# 4-Antennas.net
KiCad netlist of a schematic drawn in Altium Designer
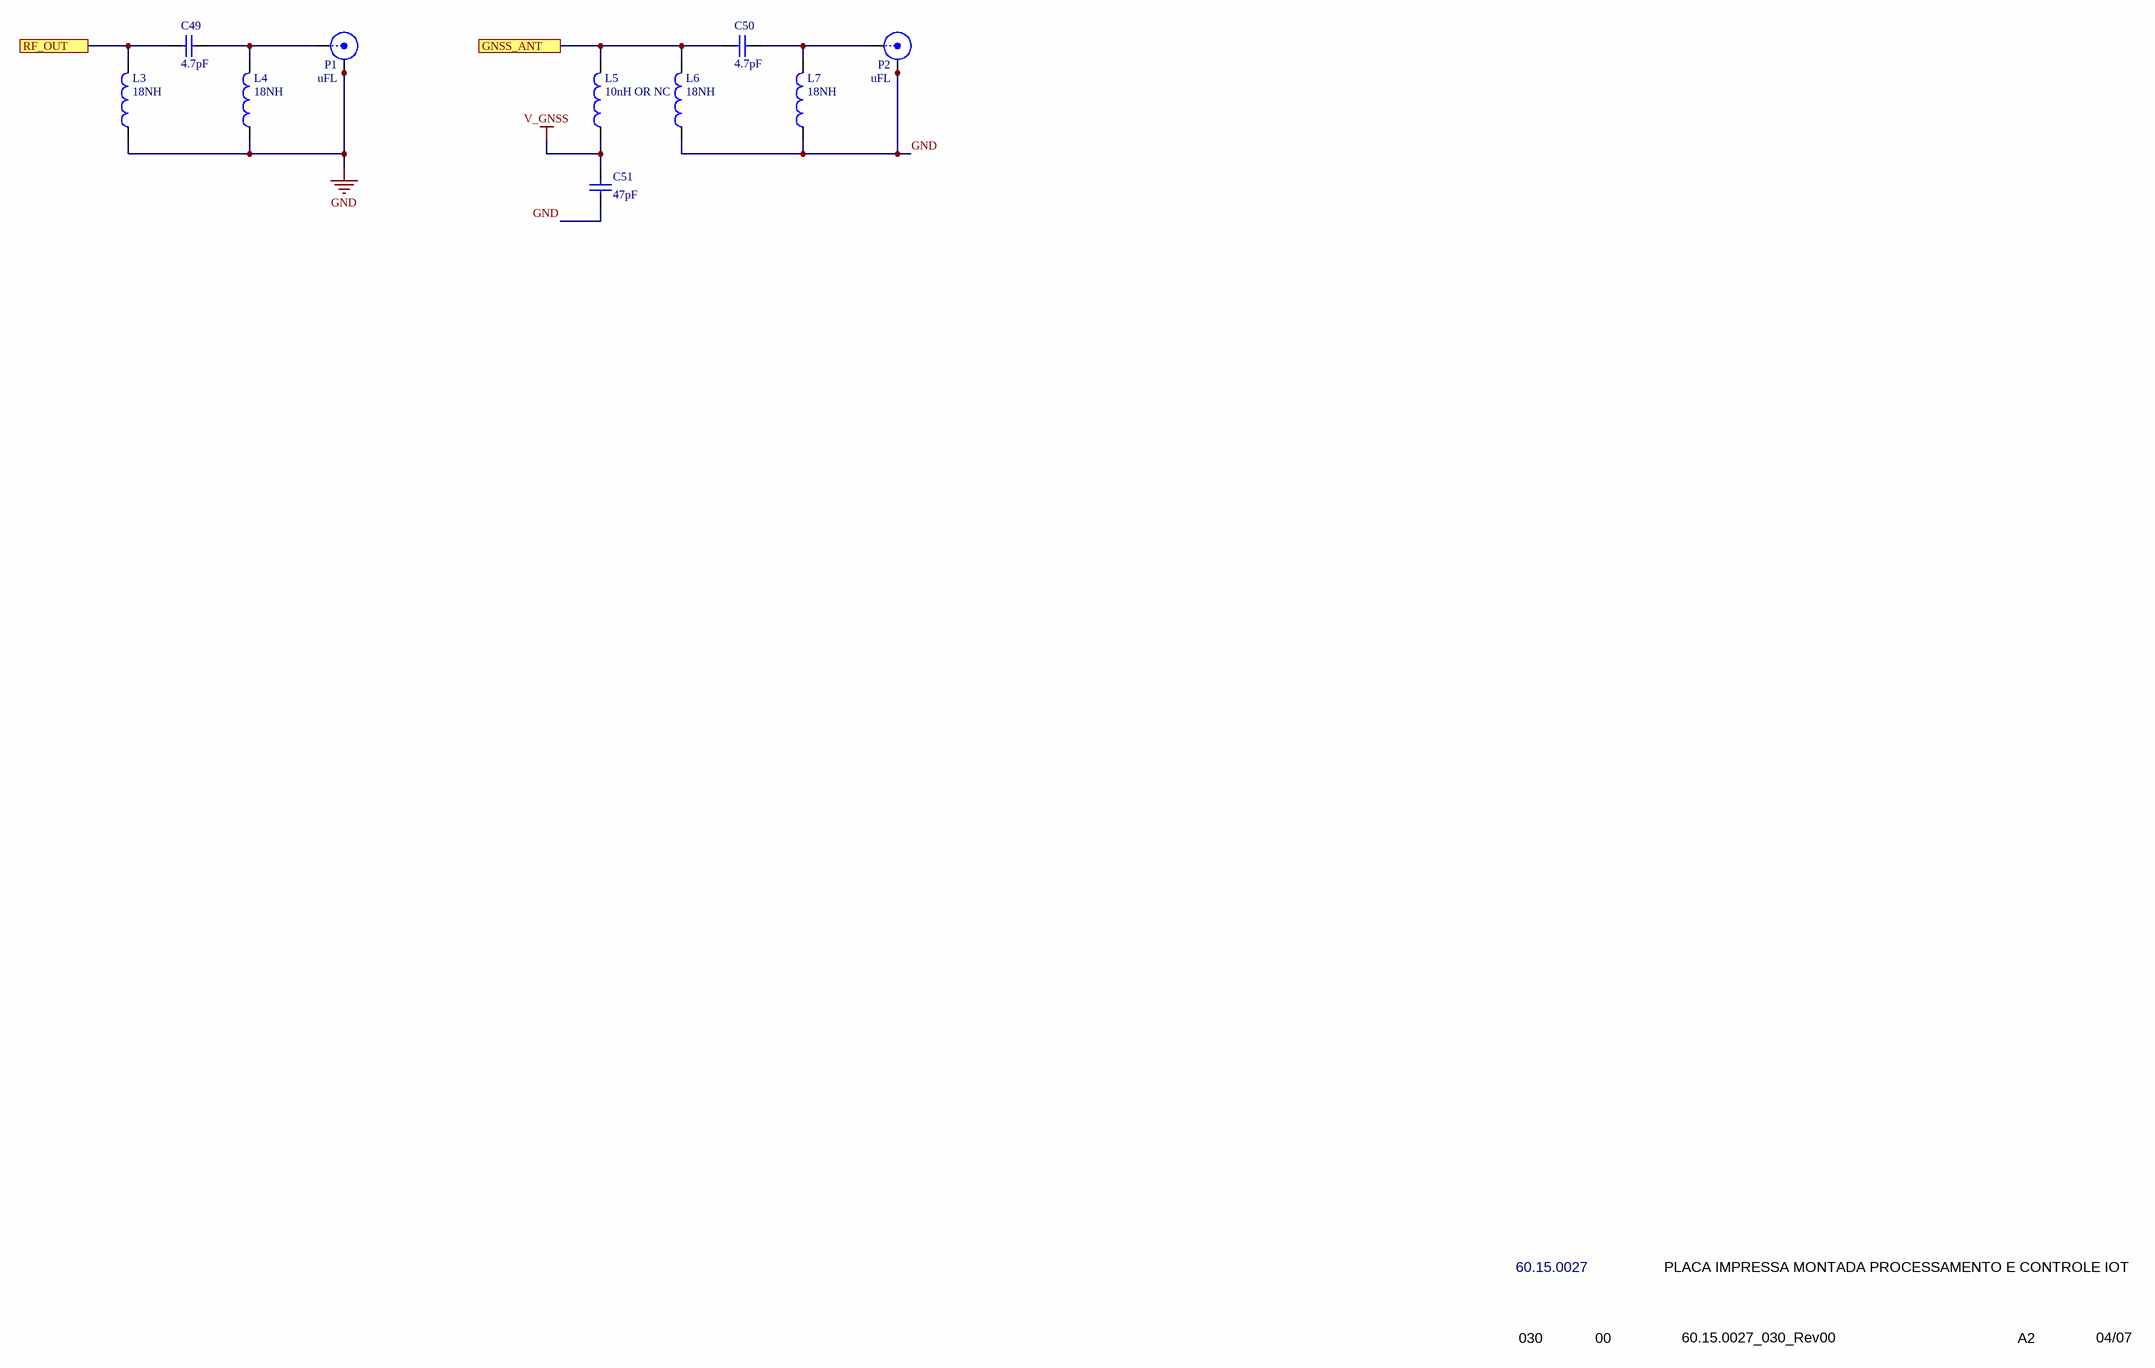
[diagram p0: 4-Antennas.SchDoc]

(export (version "E")
  (design (tool "Eeschema 10.0.6"))
  (components
    (comp (ref "C49")
      (value "16.23.0788")
      (footprint "16.23.0788")
      (description "CAPACITOR CERAMICO MULTICAMADA 4.7PF 50V C0G/NP0 0402")
      (fields (field (name "ALTIUM_UNNAMED_1") "4.7pF"))
      (libsource (lib "OMNI-CAPACITORES") (part "16.23.0788"))
    )
    (comp (ref "C50")
      (value "16.23.0788")
      (footprint "16.23.0788")
      (description "CAPACITOR CERAMICO MULTICAMADA 4.7PF 50V C0G/NP0 0402")
      (fields (field (name "ALTIUM_UNNAMED_1") "4.7pF"))
      (libsource (lib "OMNI-CAPACITORES") (part "16.23.0788"))
    )
    (comp (ref "C51")
      (value "16.23.0798")
      (footprint "16.23.0798")
      (description "CAPACITOR CERAMICO 47pF 10V 5% C0G SMD 0201")
      (fields (field (name "ALTIUM_UNNAMED_1") "47pF"))
      (libsource (lib "OMNI-CAPACITORES") (part "16.23.0798"))
    )
    (comp (ref "L3")
      (value "18NH")
      (footprint "40.12.0345")
      (description "INDUTOR FIXO 18NH 370MA 270 MOHM 0402")
      (fields (field (name "Comment") "40.12.0345"))
      (libsource (lib "OMNI-INDUTORES") (part "40.12.0345"))
    )
    (comp (ref "L4")
      (value "18NH")
      (footprint "40.12.0345")
      (description "INDUTOR FIXO 18NH 370MA 270 MOHM 0402")
      (fields (field (name "Comment") "40.12.0345"))
      (libsource (lib "OMNI-INDUTORES") (part "40.12.0345"))
    )
    (comp (ref "L5")
      (value "10nH OR NC")
      (footprint "40.12.0348")
      (description "INDUTOR FIXO 10nH 3% 500mA 260mOHM 0402")
      (fields (field (name "PART NUMBER") "LQG15HS10NH02D") (field (name "Comment") "40.12.0348"))
      (libsource (lib "OMNI-INDUTORES") (part "40.12.0348"))
    )
    (comp (ref "L6")
      (value "18NH")
      (footprint "40.12.0345")
      (description "INDUTOR FIXO 18NH 370MA 270 MOHM 0402")
      (fields (field (name "Comment") "40.12.0345"))
      (libsource (lib "OMNI-INDUTORES") (part "40.12.0345"))
    )
    (comp (ref "L7")
      (value "18NH")
      (footprint "40.12.0345")
      (description "INDUTOR FIXO 18NH 370MA 270 MOHM 0402")
      (fields (field (name "Comment") "40.12.0345"))
      (libsource (lib "OMNI-INDUTORES") (part "40.12.0345"))
    )
    (comp (ref "P1")
      (value "uFL")
      (footprint "28.20.0019")
      (description "CONECTOR MICRO COAXIAL 50 OHM SMD")
      (fields (field (name "Comment") "28.20.0019"))
      (libsource (lib "OMNI-CONECTORES") (part "28.20.0019"))
    )
    (comp (ref "P2")
      (value "uFL")
      (footprint "28.20.0019")
      (description "CONECTOR MICRO COAXIAL 50 OHM SMD")
      (fields (field (name "Comment") "28.20.0019"))
      (libsource (lib "OMNI-CONECTORES") (part "28.20.0019"))
    )
  )
  (nets
    (net (code "1") (name "/GNSS_ANT") (class "Default")
      (node (ref "C50") (pin "2") (pinfunction "2_2") (pintype "passive"))
      (node (ref "L5") (pin "2") (pinfunction "2_2") (pintype "passive"))
      (node (ref "L6") (pin "2") (pinfunction "2_2") (pintype "passive"))
    )
    (net (code "2") (name "/RF_OUT") (class "Default")
      (node (ref "C49") (pin "2") (pinfunction "2_2") (pintype "passive"))
      (node (ref "L3") (pin "2") (pinfunction "2_2") (pintype "passive"))
    )
    (net (code "3") (name "GND") (class "Default")
      (node (ref "C51") (pin "1") (pinfunction "1_1") (pintype "passive"))
      (node (ref "L3") (pin "1") (pinfunction "1_1") (pintype "passive"))
      (node (ref "L4") (pin "1") (pinfunction "1_1") (pintype "passive"))
      (node (ref "L6") (pin "1") (pinfunction "1_1") (pintype "passive"))
      (node (ref "L7") (pin "1") (pinfunction "1_1") (pintype "passive"))
      (node (ref "P1") (pin "2") (pinfunction "GND_2") (pintype "power_in"))
      (node (ref "P1") (pin "3") (pinfunction "GND_3") (pintype "power_in"))
      (node (ref "P2") (pin "2") (pinfunction "GND_2") (pintype "power_in"))
      (node (ref "P2") (pin "3") (pinfunction "GND_3") (pintype "power_in"))
    )
    (net (code "4") (name "Net-(P1-SIG)") (class "Default")
      (node (ref "C49") (pin "1") (pinfunction "1_1") (pintype "passive"))
      (node (ref "L4") (pin "2") (pinfunction "2_2") (pintype "passive"))
      (node (ref "P1") (pin "1") (pinfunction "SIG_1") (pintype "passive"))
    )
    (net (code "5") (name "Net-(P2-SIG)") (class "Default")
      (node (ref "C50") (pin "1") (pinfunction "1_1") (pintype "passive"))
      (node (ref "L7") (pin "2") (pinfunction "2_2") (pintype "passive"))
      (node (ref "P2") (pin "1") (pinfunction "SIG_1") (pintype "passive"))
    )
    (net (code "6") (name "V_GNSS") (class "Default")
      (node (ref "C51") (pin "2") (pinfunction "2_2") (pintype "passive"))
      (node (ref "L5") (pin "1") (pinfunction "1_1") (pintype "passive"))
    )
  )
)
